# fuzzface.net
KiCad netlist of a schematic drawn in EAGLE
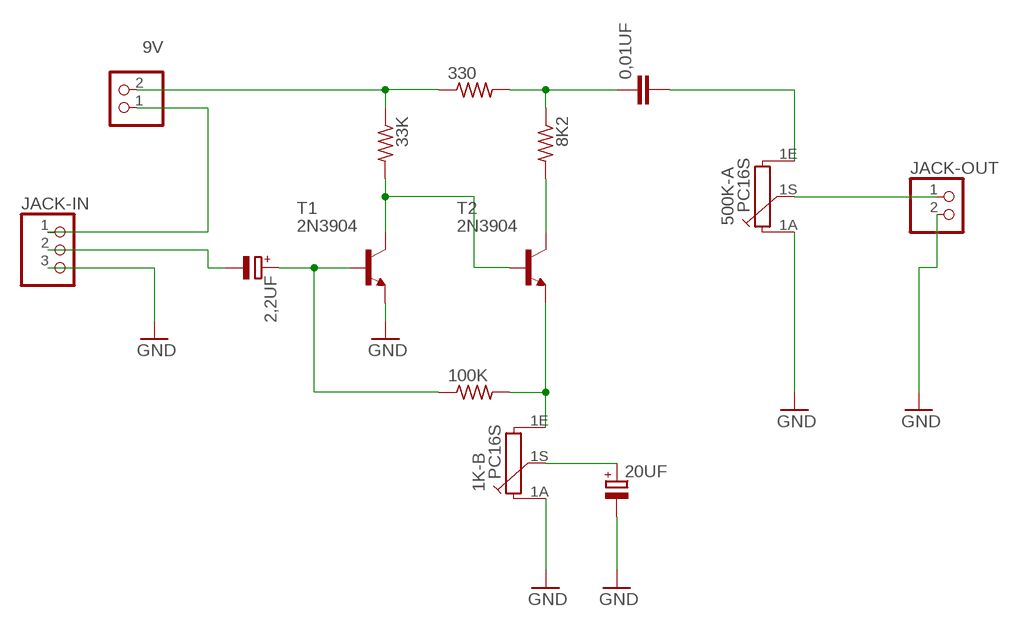
[diagram p0: schematic, sheet 1]

(export (version "E")
  (design (tool "Eeschema 10.0.6"))
  (components
    (comp (ref "0,01UF")
      (value "C2,5-3")
      (footprint "eagle-import:C2.5-3")
      (libsource (lib "eagle-import") (part "C2,5-3"))
    )
    (comp (ref "1K-B")
      (value "PC16S")
      (footprint "eagle-import:PC16S")
      (libsource (lib "eagle-import") (part "PC16S"))
    )
    (comp (ref "2,2UF")
      (value "CPOL-EUE1.8-4")
      (footprint "eagle-import:E1,8-4")
      (libsource (lib "eagle-import") (part "CPOL-EUE1.8-4"))
    )
    (comp (ref "8K2")
      (value "R-US_0204/7")
      (footprint "eagle-import:0204_7")
      (libsource (lib "eagle-import") (part "R-US_0204/7"))
    )
    (comp (ref "9V")
      (value "PINHD-1X2")
      (footprint "eagle-import:1X02")
      (libsource (lib "eagle-import") (part "PINHD-1X2"))
    )
    (comp (ref "20UF")
      (value "CPOL-EUE1.8-4")
      (footprint "eagle-import:E1,8-4")
      (libsource (lib "eagle-import") (part "CPOL-EUE1.8-4"))
    )
    (comp (ref "33K")
      (value "R-US_0204/7")
      (footprint "eagle-import:0204_7")
      (libsource (lib "eagle-import") (part "R-US_0204/7"))
    )
    (comp (ref "100K")
      (value "R-US_0204/7")
      (footprint "eagle-import:0204_7")
      (libsource (lib "eagle-import") (part "R-US_0204/7"))
    )
    (comp (ref "330")
      (value "R-US_0204/7")
      (footprint "eagle-import:0204_7")
      (libsource (lib "eagle-import") (part "R-US_0204/7"))
    )
    (comp (ref "500K-A")
      (value "PC16S")
      (footprint "eagle-import:PC16S")
      (libsource (lib "eagle-import") (part "PC16S"))
    )
    (comp (ref "JACK-IN")
      (value "PINHD-1X3")
      (footprint "eagle-import:1X03")
      (libsource (lib "eagle-import") (part "PINHD-1X3"))
    )
    (comp (ref "JACK-OUT")
      (value "PINHD-1X2")
      (footprint "eagle-import:1X02")
      (libsource (lib "eagle-import") (part "PINHD-1X2"))
    )
    (comp (ref "T1")
      (value "2N3904")
      (footprint "eagle-import:TO92")
      (libsource (lib "eagle-import") (part "2N3904"))
    )
    (comp (ref "T2")
      (value "2N3904")
      (footprint "eagle-import:TO92")
      (libsource (lib "eagle-import") (part "2N3904"))
    )
  )
  (nets
    (net (code "1") (name "GND") (class "Default")
      (node (ref "1K-B") (pin "1A") (pinfunction "1A_1A") (pintype "passive"))
      (node (ref "20UF") (pin "-") (pinfunction "-_-") (pintype "passive"))
      (node (ref "500K-A") (pin "1A") (pinfunction "1A_1A") (pintype "passive"))
      (node (ref "JACK-IN") (pin "3") (pinfunction "3_3") (pintype "passive"))
      (node (ref "JACK-OUT") (pin "2") (pinfunction "2_2") (pintype "passive"))
      (node (ref "T1") (pin "3") (pinfunction "E_3") (pintype "passive"))
    )
    (net (code "2") (name "Net-(0,01UF-Pad1)") (class "Default")
      (node (ref "0,01UF") (pin "1") (pinfunction "1_1") (pintype "passive"))
      (node (ref "330") (pin "2") (pinfunction "2_2") (pintype "passive"))
      (node (ref "8K2") (pin "1") (pinfunction "1_1") (pintype "passive"))
    )
    (net (code "3") (name "Net-(0,01UF-Pad2)") (class "Default")
      (node (ref "0,01UF") (pin "2") (pinfunction "2_2") (pintype "passive"))
      (node (ref "500K-A") (pin "1E") (pinfunction "1E_1E") (pintype "passive"))
    )
    (net (code "4") (name "Net-(1K-B-Pad1S)") (class "Default")
      (node (ref "1K-B") (pin "1S") (pinfunction "1S_1S") (pintype "passive"))
      (node (ref "20UF") (pin "+") (pinfunction "+_+") (pintype "passive"))
    )
    (net (code "5") (name "Net-(2,2UF-Pad-)") (class "Default")
      (node (ref "2,2UF") (pin "-") (pinfunction "-_-") (pintype "passive"))
      (node (ref "JACK-IN") (pin "2") (pinfunction "2_2") (pintype "passive"))
    )
    (net (code "6") (name "Net-(9V-Pad1)") (class "Default")
      (node (ref "9V") (pin "1") (pinfunction "1_1") (pintype "passive"))
      (node (ref "JACK-IN") (pin "1") (pinfunction "1_1") (pintype "passive"))
    )
    (net (code "7") (name "Net-(330-Pad1)") (class "Default")
      (node (ref "330") (pin "1") (pinfunction "1_1") (pintype "passive"))
      (node (ref "33K") (pin "1") (pinfunction "1_1") (pintype "passive"))
      (node (ref "9V") (pin "2") (pinfunction "2_2") (pintype "passive"))
    )
    (net (code "8") (name "Net-(500K-A-Pad1S)") (class "Default")
      (node (ref "500K-A") (pin "1S") (pinfunction "1S_1S") (pintype "passive"))
      (node (ref "JACK-OUT") (pin "1") (pinfunction "1_1") (pintype "passive"))
    )
    (net (code "9") (name "Net-(T1-B)") (class "Default")
      (node (ref "100K") (pin "1") (pinfunction "1_1") (pintype "passive"))
      (node (ref "2,2UF") (pin "+") (pinfunction "+_+") (pintype "passive"))
      (node (ref "T1") (pin "2") (pinfunction "B_2") (pintype "passive"))
    )
    (net (code "10") (name "Net-(T1-C)") (class "Default")
      (node (ref "33K") (pin "2") (pinfunction "2_2") (pintype "passive"))
      (node (ref "T1") (pin "1") (pinfunction "C_1") (pintype "passive"))
      (node (ref "T2") (pin "2") (pinfunction "B_2") (pintype "passive"))
    )
    (net (code "11") (name "Net-(T2-C)") (class "Default")
      (node (ref "8K2") (pin "2") (pinfunction "2_2") (pintype "passive"))
      (node (ref "T2") (pin "1") (pinfunction "C_1") (pintype "passive"))
    )
    (net (code "12") (name "Net-(T2-E)") (class "Default")
      (node (ref "100K") (pin "2") (pinfunction "2_2") (pintype "passive"))
      (node (ref "1K-B") (pin "1E") (pinfunction "1E_1E") (pintype "passive"))
      (node (ref "T2") (pin "3") (pinfunction "E_3") (pintype "passive"))
    )
  )
)
